# RMII_Ethernet.net
KiCad netlist of a schematic drawn in Altium Designer
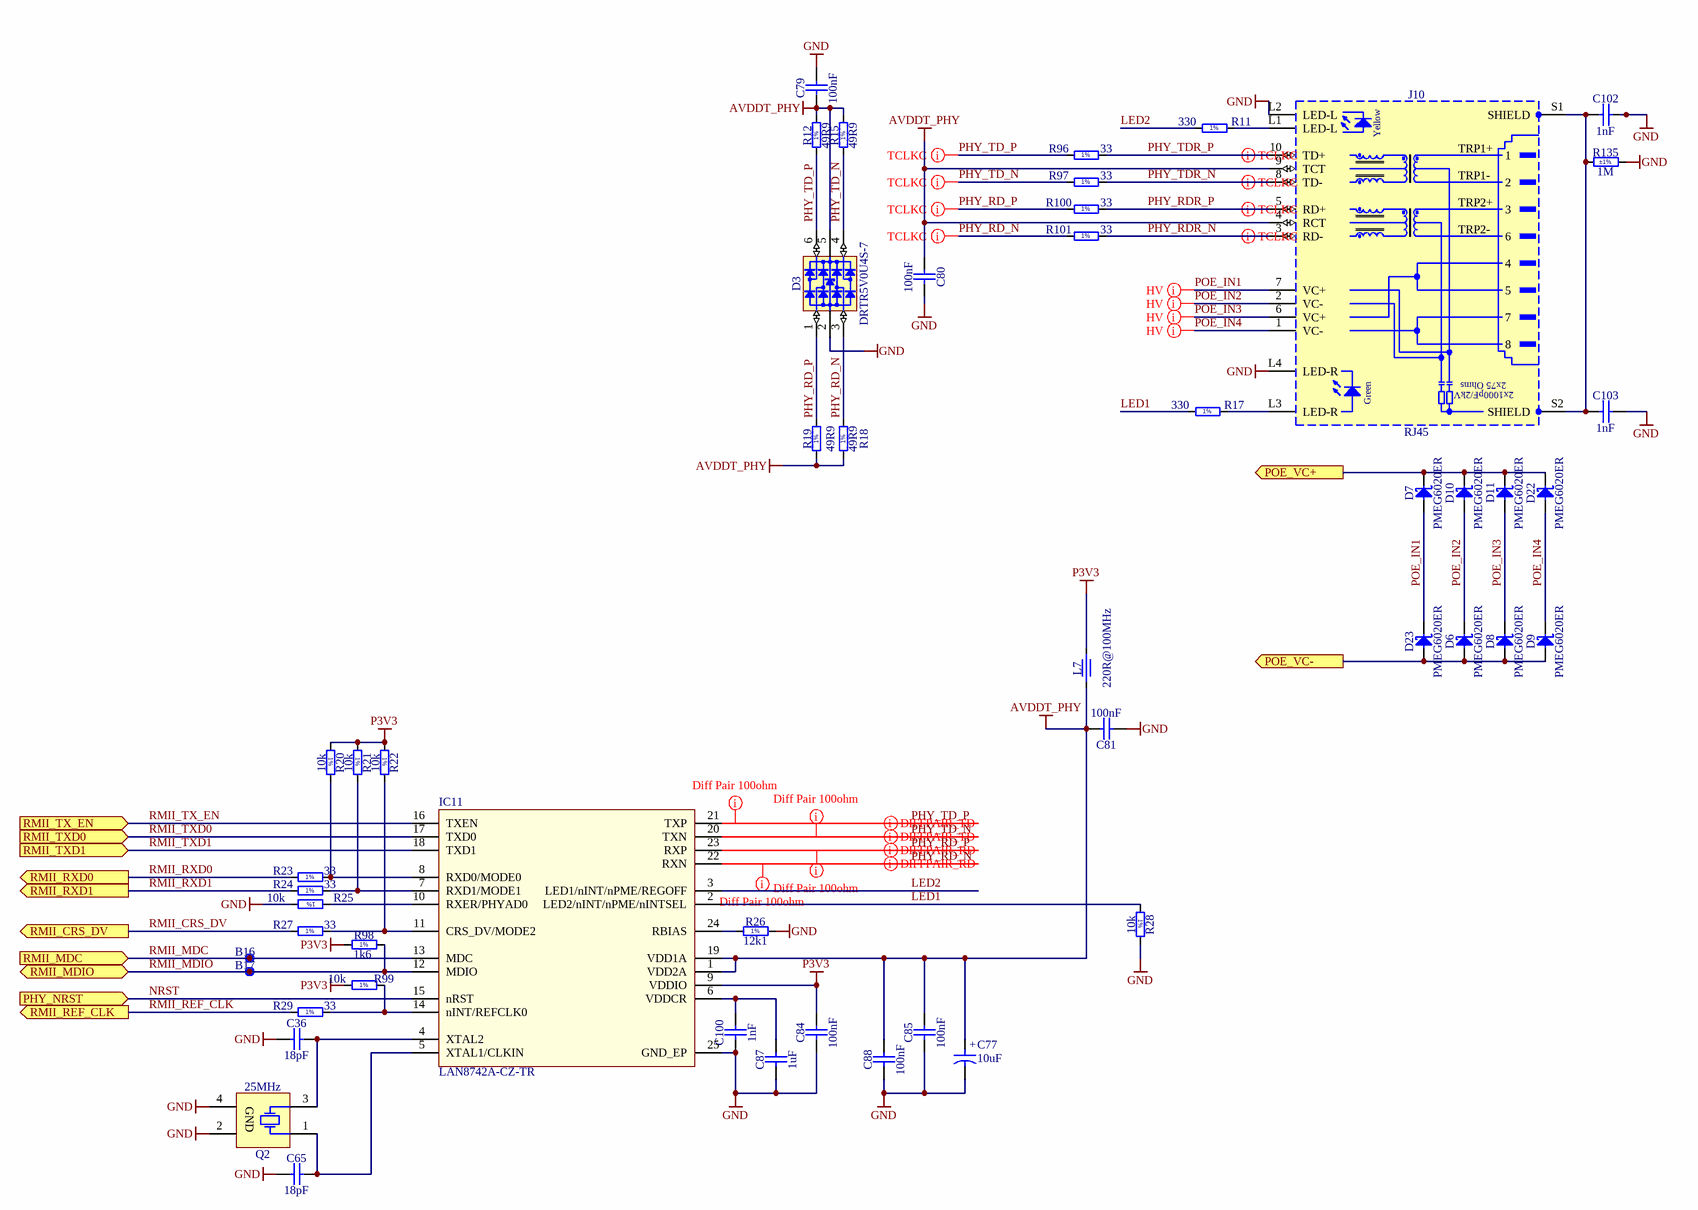
[diagram p0: RMII_Ethernet.SchDoc]

(export (version "E")
  (design (tool "Eeschema 10.0.6"))
  (components
    (comp (ref "B16")
      (value "SMD Pad")
      (footprint "C100")
      (description "Through Hole Pad")
      (fields (field (name "PART NUMBER") "SMD_PAD_D1MM") (field (name "AUTHOR") "CERN DEM JLC"))
      (libsource (lib "Eletro-mechanical") (part "Single SMD Pad (Round)"))
    )
    (comp (ref "B17")
      (value "SMD Pad")
      (footprint "C100")
      (description "Through Hole Pad")
      (fields (field (name "PART NUMBER") "SMD_PAD_D1MM") (field (name "AUTHOR") "CERN DEM JLC"))
      (libsource (lib "Eletro-mechanical") (part "Single SMD Pad (Round)"))
    )
    (comp (ref "C36")
      (value "18pF")
      (footprint "CAPC1005X55N")
      (description "Non-polarised capacitor")
      (fields
        (field (name "PART NUMBER") "CC0402_18PF_50V_5%_C0G")
        (field (name "VOLTAGE") "50V")
        (field (name "AUTHOR") "CERN DEM JLC")
      )
      (libsource (lib "Capacitors") (part "Capacitor - non polarized"))
    )
    (comp (ref "C65")
      (value "18pF")
      (footprint "CAPC1005X55N")
      (description "Non-polarised capacitor")
      (fields
        (field (name "PART NUMBER") "CC0402_18PF_50V_5%_C0G")
        (field (name "VOLTAGE") "50V")
        (field (name "AUTHOR") "CERN DEM JLC")
      )
      (libsource (lib "Capacitors") (part "Capacitor - non polarized"))
    )
    (comp (ref "C77")
      (value "10uF")
      (footprint "CAPMP3216X180N")
      (description "Polarised capacitor")
      (fields
        (field (name "PART NUMBER") "CTE3216-18_10UF_16V_20%_AVX_TCJ")
        (field (name "VOLTAGE") "16V")
        (field (name "AUTHOR") "CERN DEM JLC")
      )
      (libsource (lib "Capacitors") (part "Capacitor - polarized"))
    )
    (comp (ref "C79")
      (value "100nF")
      (footprint "CAPC1005X55N")
      (description "Non-polarised capacitor")
      (fields
        (field (name "PART NUMBER") "CC0402_100NF_16V_10%_X5R")
        (field (name "VOLTAGE") "16V")
        (field (name "AUTHOR") "CERN DEM JLC")
      )
      (libsource (lib "Capacitors") (part "Capacitor - non polarized"))
    )
    (comp (ref "C80")
      (value "100nF")
      (footprint "CAPC1005X55N")
      (description "Non-polarised capacitor")
      (fields
        (field (name "PART NUMBER") "CC0402_100NF_16V_10%_X5R")
        (field (name "VOLTAGE") "16V")
        (field (name "AUTHOR") "CERN DEM JLC")
      )
      (libsource (lib "Capacitors") (part "Capacitor - non polarized"))
    )
    (comp (ref "C81")
      (value "100nF")
      (footprint "CAPC1005X55N")
      (description "Non-polarised capacitor")
      (fields
        (field (name "PART NUMBER") "CC0402_100NF_16V_10%_X5R")
        (field (name "VOLTAGE") "16V")
        (field (name "AUTHOR") "CERN DEM JLC")
      )
      (libsource (lib "Capacitors") (part "Capacitor - non polarized"))
    )
    (comp (ref "C84")
      (value "100nF")
      (footprint "CAPC1005X55N")
      (description "Non-polarised capacitor")
      (fields
        (field (name "PART NUMBER") "CC0402_100NF_16V_10%_X5R")
        (field (name "VOLTAGE") "16V")
        (field (name "AUTHOR") "CERN DEM JLC")
      )
      (libsource (lib "Capacitors") (part "Capacitor - non polarized"))
    )
    (comp (ref "C85")
      (value "100nF")
      (footprint "CAPC1005X55N")
      (description "Non-polarised capacitor")
      (fields
        (field (name "PART NUMBER") "CC0402_100NF_16V_10%_X5R")
        (field (name "VOLTAGE") "16V")
        (field (name "AUTHOR") "CERN DEM JLC")
      )
      (libsource (lib "Capacitors") (part "Capacitor - non polarized"))
    )
    (comp (ref "C87")
      (value "1uF")
      (footprint "CAPC1608X87N")
      (description "Non-polarised capacitor")
      (fields
        (field (name "PART NUMBER") "CC0603_1UF_16V_10%_X7R")
        (field (name "VOLTAGE") "16V")
        (field (name "AUTHOR") "CERN DEM JLC")
      )
      (libsource (lib "Capacitors") (part "Capacitor - non polarized"))
    )
    (comp (ref "C88")
      (value "100nF")
      (footprint "CAPC1005X55N")
      (description "Non-polarised capacitor")
      (fields
        (field (name "PART NUMBER") "CC0402_100NF_16V_10%_X5R")
        (field (name "VOLTAGE") "16V")
        (field (name "AUTHOR") "CERN DEM JLC")
      )
      (libsource (lib "Capacitors") (part "Capacitor - non polarized"))
    )
    (comp (ref "C100")
      (value "1nF")
      (footprint "CAPC1005X55N")
      (description "Non-polarised capacitor")
      (fields
        (field (name "PART NUMBER") "CC0402_1NF_50V_10%_X7R")
        (field (name "VOLTAGE") "50V")
        (field (name "AUTHOR") "CERN DEM JLC")
      )
      (libsource (lib "Capacitors") (part "Capacitor - non polarized"))
    )
    (comp (ref "C102")
      (value "1nF")
      (footprint "CAPC2012X135N")
      (description "Non-polarised capacitor")
      (fields
        (field (name "PART NUMBER") "CC0805_1NF_50V_10%_X7R")
        (field (name "VOLTAGE") "50V")
        (field (name "AUTHOR") "CERN DEM JLC")
      )
      (libsource (lib "Capacitors") (part "Capacitor - non polarized"))
    )
    (comp (ref "C103")
      (value "1nF")
      (footprint "CAPC2012X135N")
      (description "Non-polarised capacitor")
      (fields
        (field (name "PART NUMBER") "CC0805_1NF_50V_10%_X7R")
        (field (name "VOLTAGE") "50V")
        (field (name "AUTHOR") "CERN DEM JLC")
      )
      (libsource (lib "Capacitors") (part "Capacitor - non polarized"))
    )
    (comp (ref "D3")
      (value "DRTR5V0U4S-7")
      (footprint "SOT65P210X110-6N")
      (description "Integrated Quad Ultra-Low Capacitance ESD Protection")
      (fields (field (name "MANUFACTURER") "DIODES") (field (name "AUTHOR") "GK"))
      (libsource (lib "Diodes") (part "D_TVS_DRTR5V0U4S-7"))
    )
    (comp (ref "D6")
      (value "PMEG6020ER")
      (footprint "SODFL3517X110N")
      (description "Schottky Diode")
      (fields
        (field (name "VOLTAGE") "60V")
        (field (name "POWER") "2A")
        (field (name "AUTHOR") "CERN DEM JMW")
      )
      (libsource (lib "ICs And Semiconductors") (part "Diode Schottky"))
    )
    (comp (ref "D7")
      (value "PMEG6020ER")
      (footprint "SODFL3517X110N")
      (description "Schottky Diode")
      (fields
        (field (name "VOLTAGE") "60V")
        (field (name "POWER") "2A")
        (field (name "AUTHOR") "CERN DEM JMW")
      )
      (libsource (lib "ICs And Semiconductors") (part "Diode Schottky"))
    )
    (comp (ref "D8")
      (value "PMEG6020ER")
      (footprint "SODFL3517X110N")
      (description "Schottky Diode")
      (fields
        (field (name "VOLTAGE") "60V")
        (field (name "POWER") "2A")
        (field (name "AUTHOR") "CERN DEM JMW")
      )
      (libsource (lib "ICs And Semiconductors") (part "Diode Schottky"))
    )
    (comp (ref "D9")
      (value "PMEG6020ER")
      (footprint "SODFL3517X110N")
      (description "Schottky Diode")
      (fields
        (field (name "VOLTAGE") "60V")
        (field (name "POWER") "2A")
        (field (name "AUTHOR") "CERN DEM JMW")
      )
      (libsource (lib "ICs And Semiconductors") (part "Diode Schottky"))
    )
    (comp (ref "D10")
      (value "PMEG6020ER")
      (footprint "SODFL3517X110N")
      (description "Schottky Diode")
      (fields
        (field (name "VOLTAGE") "60V")
        (field (name "POWER") "2A")
        (field (name "AUTHOR") "CERN DEM JMW")
      )
      (libsource (lib "ICs And Semiconductors") (part "Diode Schottky"))
    )
    (comp (ref "D11")
      (value "PMEG6020ER")
      (footprint "SODFL3517X110N")
      (description "Schottky Diode")
      (fields
        (field (name "VOLTAGE") "60V")
        (field (name "POWER") "2A")
        (field (name "AUTHOR") "CERN DEM JMW")
      )
      (libsource (lib "ICs And Semiconductors") (part "Diode Schottky"))
    )
    (comp (ref "D22")
      (value "PMEG6020ER")
      (footprint "SODFL3517X110N")
      (description "Schottky Diode")
      (fields
        (field (name "VOLTAGE") "60V")
        (field (name "POWER") "2A")
        (field (name "AUTHOR") "CERN DEM JMW")
      )
      (libsource (lib "ICs And Semiconductors") (part "Diode Schottky"))
    )
    (comp (ref "D23")
      (value "PMEG6020ER")
      (footprint "SODFL3517X110N")
      (description "Schottky Diode")
      (fields
        (field (name "VOLTAGE") "60V")
        (field (name "POWER") "2A")
        (field (name "AUTHOR") "CERN DEM JMW")
      )
      (libsource (lib "ICs And Semiconductors") (part "Diode Schottky"))
    )
    (comp (ref "IC11")
      (value "LAN8742A-CZ-TR")
      (footprint "QFN24_0R5_4X4")
      (libsource (lib "LIBRARY_SCH") (part "IFC_LAN8742A"))
    )
    (comp (ref "J10")
      (value "RJ45")
      (footprint "ABRACON_ARJM11C7-114-BA-EW2")
      (description "MagJack 10/100BaseT, PoE+, 1X1, OG/Y, -40 to 85*C, Tab Up, RoHS")
      (fields
        (field (name "PART NUMBER") "ARJM11C7-114-BA-EW2")
        (field (name "MANUFACTURER") "Abracon")
        (field (name "AUTHOR") "GK")
      )
      (libsource (lib "LIBRARY_SCH") (part "CON_ETH_POE_ARJM11C7"))
    )
    (comp (ref "L7")
      (value "220R@100MHz")
      (footprint "INDC1005X55N")
      (fields
        (field (name "PART NUMBER") "IND0402_MURATA_BLM15HB221SN1")
        (field (name "POWER") "250mA")
        (field (name "TOLERANCE") "±25%")
        (field (name "AUTHOR") "CERN DEM JLC")
      )
      (libsource (lib "Inductors & Transformers") (part "Ferrite Bead"))
    )
    (comp (ref "Q2")
      (value "25MHz")
      (footprint "XTAL_EPSON_TSX-3225")
      (description "Crystal 4 pins 1=XTAL Control 2=GND3=XTAL 4=GND")
      (fields
        (field (name "PART NUMBER") "XTAL_25MHZ_EPSON_TSX-3225 25.0000MF10Z-AC")
        (field (name "MANUFACTURER") "EPSON")
        (field (name "AUTHOR") "CERN DEM JLC")
      )
      (libsource (lib "ICs And Semiconductors") (part "Quartz Crystal 1X 2GND 3X 4GND"))
    )
    (comp (ref "R11")
      (value "330")
      (footprint "RESC1005X40N")
      (description "Resistor - 1%")
      (fields
        (field (name "PART NUMBER") "R0402_330R_1%_0.0625W_100PPM")
        (field (name "POWER") "0.0625W")
        (field (name "AUTHOR") "CERN DEM JLC")
      )
      (libsource (lib "Resistors") (part "Resistor - 1%"))
    )
    (comp (ref "R12")
      (value "49R9")
      (footprint "RESC1005X40N")
      (description "Resistor - 1%")
      (fields
        (field (name "PART NUMBER") "R0402_49R9_1%_0.0625W_100PPM")
        (field (name "POWER") "0.0625W")
        (field (name "AUTHOR") "CERN DEM JLC")
      )
      (libsource (lib "Resistors") (part "Resistor - 1%"))
    )
    (comp (ref "R15")
      (value "49R9")
      (footprint "RESC1005X40N")
      (description "Resistor - 1%")
      (fields
        (field (name "PART NUMBER") "R0402_49R9_1%_0.0625W_100PPM")
        (field (name "POWER") "0.0625W")
        (field (name "AUTHOR") "CERN DEM JLC")
      )
      (libsource (lib "Resistors") (part "Resistor - 1%"))
    )
    (comp (ref "R17")
      (value "330")
      (footprint "RESC1005X40N")
      (description "Resistor - 1%")
      (fields
        (field (name "PART NUMBER") "R0402_330R_1%_0.0625W_100PPM")
        (field (name "POWER") "0.0625W")
        (field (name "AUTHOR") "CERN DEM JLC")
      )
      (libsource (lib "Resistors") (part "Resistor - 1%"))
    )
    (comp (ref "R18")
      (value "49R9")
      (footprint "RESC1005X40N")
      (description "Resistor - 1%")
      (fields
        (field (name "PART NUMBER") "R0402_49R9_1%_0.0625W_100PPM")
        (field (name "POWER") "0.0625W")
        (field (name "AUTHOR") "CERN DEM JLC")
      )
      (libsource (lib "Resistors") (part "Resistor - 1%"))
    )
    (comp (ref "R19")
      (value "49R9")
      (footprint "RESC1005X40N")
      (description "Resistor - 1%")
      (fields
        (field (name "PART NUMBER") "R0402_49R9_1%_0.0625W_100PPM")
        (field (name "POWER") "0.0625W")
        (field (name "AUTHOR") "CERN DEM JLC")
      )
      (libsource (lib "Resistors") (part "Resistor - 1%"))
    )
    (comp (ref "R20")
      (value "10k")
      (footprint "RESC1005X40N")
      (description "Resistor - 1%")
      (fields
        (field (name "PART NUMBER") "R0402_10K_1%_0.0625W_100PPM")
        (field (name "POWER") "0.0625W")
        (field (name "AUTHOR") "CERN DEM JLC")
      )
      (libsource (lib "Resistors") (part "Resistor - 1%"))
    )
    (comp (ref "R21")
      (value "10k")
      (footprint "RESC1005X40N")
      (description "Resistor - 1%")
      (fields
        (field (name "PART NUMBER") "R0402_10K_1%_0.0625W_100PPM")
        (field (name "POWER") "0.0625W")
        (field (name "AUTHOR") "CERN DEM JLC")
      )
      (libsource (lib "Resistors") (part "Resistor - 1%"))
    )
    (comp (ref "R22")
      (value "10k")
      (footprint "RESC1005X40N")
      (description "Resistor - 1%")
      (fields
        (field (name "PART NUMBER") "R0402_10K_1%_0.0625W_100PPM")
        (field (name "POWER") "0.0625W")
        (field (name "AUTHOR") "CERN DEM JLC")
      )
      (libsource (lib "Resistors") (part "Resistor - 1%"))
    )
    (comp (ref "R23")
      (value "33")
      (footprint "RESC1005X40N")
      (description "Resistor - 1%")
      (fields
        (field (name "PART NUMBER") "R0402_33R_1%_0.0625W_100PPM")
        (field (name "POWER") "0.0625W")
        (field (name "AUTHOR") "CERN DEM JLC")
      )
      (libsource (lib "Resistors") (part "Resistor - 1%"))
    )
    (comp (ref "R24")
      (value "33")
      (footprint "RESC1005X40N")
      (description "Resistor - 1%")
      (fields
        (field (name "PART NUMBER") "R0402_33R_1%_0.0625W_100PPM")
        (field (name "POWER") "0.0625W")
        (field (name "AUTHOR") "CERN DEM JLC")
      )
      (libsource (lib "Resistors") (part "Resistor - 1%"))
    )
    (comp (ref "R25")
      (value "10k")
      (footprint "RESC1005X40N")
      (description "Resistor - 1%")
      (fields
        (field (name "PART NUMBER") "R0402_10K_1%_0.0625W_100PPM")
        (field (name "POWER") "0.0625W")
        (field (name "AUTHOR") "CERN DEM JLC")
      )
      (libsource (lib "Resistors") (part "Resistor - 1%"))
    )
    (comp (ref "R26")
      (value "12k1")
      (footprint "RESC1005X40N")
      (description "Resistor - 1%")
      (fields
        (field (name "PART NUMBER") "R0402_12K1_1%_0.0625W_100PPM")
        (field (name "POWER") "0.0625W")
        (field (name "AUTHOR") "CERN DEM JLC")
      )
      (libsource (lib "Resistors") (part "Resistor - 1%"))
    )
    (comp (ref "R27")
      (value "33")
      (footprint "RESC1005X40N")
      (description "Resistor - 1%")
      (fields
        (field (name "PART NUMBER") "R0402_33R_1%_0.0625W_100PPM")
        (field (name "POWER") "0.0625W")
        (field (name "AUTHOR") "CERN DEM JLC")
      )
      (libsource (lib "Resistors") (part "Resistor - 1%"))
    )
    (comp (ref "R28")
      (value "10k")
      (footprint "RESC1005X40N")
      (description "Resistor - 1%")
      (fields
        (field (name "PART NUMBER") "R0402_10K_1%_0.0625W_100PPM")
        (field (name "POWER") "0.0625W")
        (field (name "AUTHOR") "CERN DEM JLC")
      )
      (libsource (lib "Resistors") (part "Resistor - 1%"))
    )
    (comp (ref "R29")
      (value "33")
      (footprint "RESC1005X40N")
      (description "Resistor - 1%")
      (fields
        (field (name "PART NUMBER") "R0402_33R_1%_0.0625W_100PPM")
        (field (name "POWER") "0.0625W")
        (field (name "AUTHOR") "CERN DEM JLC")
      )
      (libsource (lib "Resistors") (part "Resistor - 1%"))
    )
    (comp (ref "R96")
      (value "33")
      (footprint "RESC1005X40N")
      (description "Resistor - 1%")
      (fields
        (field (name "PART NUMBER") "R0402_33R_1%_0.0625W_100PPM")
        (field (name "POWER") "0.0625W")
        (field (name "AUTHOR") "CERN DEM JLC")
      )
      (libsource (lib "Resistors") (part "Resistor - 1%"))
    )
    (comp (ref "R97")
      (value "33")
      (footprint "RESC1005X40N")
      (description "Resistor - 1%")
      (fields
        (field (name "PART NUMBER") "R0402_33R_1%_0.0625W_100PPM")
        (field (name "POWER") "0.0625W")
        (field (name "AUTHOR") "CERN DEM JLC")
      )
      (libsource (lib "Resistors") (part "Resistor - 1%"))
    )
    (comp (ref "R98")
      (value "1k6")
      (footprint "RESC1005X40N")
      (description "Resistor - 1%")
      (fields
        (field (name "PART NUMBER") "R0402_1K6_1%_0.0625W_100PPM")
        (field (name "POWER") "0.0625W")
        (field (name "AUTHOR") "CERN DEM JLC")
      )
      (libsource (lib "Resistors") (part "Resistor - 1%"))
    )
    (comp (ref "R99")
      (value "10k")
      (footprint "RESC1005X40N")
      (description "Resistor - 1%")
      (fields
        (field (name "PART NUMBER") "R0402_10K_1%_0.0625W_100PPM")
        (field (name "POWER") "0.0625W")
        (field (name "AUTHOR") "CERN DEM JLC")
      )
      (libsource (lib "Resistors") (part "Resistor - 1%"))
    )
    (comp (ref "R100")
      (value "33")
      (footprint "RESC1005X40N")
      (description "Resistor - 1%")
      (fields
        (field (name "PART NUMBER") "R0402_33R_1%_0.0625W_100PPM")
        (field (name "POWER") "0.0625W")
        (field (name "AUTHOR") "CERN DEM JLC")
      )
      (libsource (lib "Resistors") (part "Resistor - 1%"))
    )
    (comp (ref "R101")
      (value "33")
      (footprint "RESC1005X40N")
      (description "Resistor - 1%")
      (fields
        (field (name "PART NUMBER") "R0402_33R_1%_0.0625W_100PPM")
        (field (name "POWER") "0.0625W")
        (field (name "AUTHOR") "CERN DEM JLC")
      )
      (libsource (lib "Resistors") (part "Resistor - 1%"))
    )
    (comp (ref "R135")
      (value "1M")
      (footprint "RESC1608X55N")
      (description "Resistor - 1%")
      (fields
        (field (name "TOLERANCE") "±1%")
        (field (name "PART NUMBER") "R0603_1M_1%_0.1W_100PPM")
        (field (name "POWER") "0.1W")
        (field (name "AUTHOR") "CERN DEM JLC")
      )
      (libsource (lib "") (part "Resistor - 1%_1"))
    )
  )
  (nets
    (net (code "1") (name "/LED1") (class "Default")
      (node (ref "IC11") (pin "2") (pinfunction "LED2/nINT/nPME/nINTSEL_2") (pintype "passive"))
      (node (ref "R17") (pin "1") (pinfunction "1_1") (pintype "passive"))
      (node (ref "R28") (pin "1") (pinfunction "1_1") (pintype "passive"))
    )
    (net (code "2") (name "/LED2") (class "Default")
      (node (ref "IC11") (pin "3") (pinfunction "LED1/nINT/nPME/REGOFF_3") (pintype "passive"))
      (node (ref "R11") (pin "1") (pinfunction "1_1") (pintype "passive"))
    )
    (net (code "3") (name "/NRST") (class "Default")
      (node (ref "IC11") (pin "15") (pinfunction "nRST_15") (pintype "passive"))
    )
    (net (code "4") (name "/PHY_RDR_N") (class "Default")
      (node (ref "J10") (pin "3") (pinfunction "RD-_3") (pintype "bidirectional"))
      (node (ref "R101") (pin "2") (pinfunction "2_2") (pintype "passive"))
    )
    (net (code "5") (name "/PHY_RDR_P") (class "Default")
      (node (ref "J10") (pin "5") (pinfunction "RD+_5") (pintype "bidirectional"))
      (node (ref "R100") (pin "2") (pinfunction "2_2") (pintype "passive"))
    )
    (net (code "6") (name "/PHY_RD_N") (class "Default")
      (node (ref "D3") (pin "3") (pinfunction "I/O2_3") (pintype "bidirectional"))
      (node (ref "IC11") (pin "22") (pinfunction "RXN_22") (pintype "passive"))
      (node (ref "R101") (pin "1") (pinfunction "1_1") (pintype "passive"))
      (node (ref "R18") (pin "2") (pinfunction "2_2") (pintype "passive"))
    )
    (net (code "7") (name "/PHY_RD_P") (class "Default")
      (node (ref "D3") (pin "1") (pinfunction "I/O1_1") (pintype "bidirectional"))
      (node (ref "IC11") (pin "23") (pinfunction "RXP_23") (pintype "passive"))
      (node (ref "R100") (pin "1") (pinfunction "1_1") (pintype "passive"))
      (node (ref "R19") (pin "2") (pinfunction "2_2") (pintype "passive"))
    )
    (net (code "8") (name "/PHY_TDR_N") (class "Default")
      (node (ref "J10") (pin "8") (pinfunction "TD-_8") (pintype "bidirectional"))
      (node (ref "R97") (pin "2") (pinfunction "2_2") (pintype "passive"))
    )
    (net (code "9") (name "/PHY_TDR_P") (class "Default")
      (node (ref "J10") (pin "10") (pinfunction "TD+_10") (pintype "bidirectional"))
      (node (ref "R96") (pin "2") (pinfunction "2_2") (pintype "passive"))
    )
    (net (code "10") (name "/PHY_TD_N") (class "Default")
      (node (ref "D3") (pin "4") (pinfunction "I/O3_4") (pintype "bidirectional"))
      (node (ref "IC11") (pin "20") (pinfunction "TXN_20") (pintype "passive"))
      (node (ref "R15") (pin "1") (pinfunction "1_1") (pintype "passive"))
      (node (ref "R97") (pin "1") (pinfunction "1_1") (pintype "passive"))
    )
    (net (code "11") (name "/PHY_TD_P") (class "Default")
      (node (ref "D3") (pin "6") (pinfunction "I/O4_6") (pintype "bidirectional"))
      (node (ref "IC11") (pin "21") (pinfunction "TXP_21") (pintype "passive"))
      (node (ref "R12") (pin "1") (pinfunction "1_1") (pintype "passive"))
      (node (ref "R96") (pin "1") (pinfunction "1_1") (pintype "passive"))
    )
    (net (code "12") (name "/POE_IN1") (class "Default")
      (node (ref "D23") (pin "1") (pinfunction "C_1") (pintype "passive"))
      (node (ref "D7") (pin "2") (pinfunction "A_2") (pintype "passive"))
      (node (ref "J10") (pin "7") (pinfunction "VC+_7") (pintype "passive"))
    )
    (net (code "13") (name "/POE_IN2") (class "Default")
      (node (ref "D10") (pin "2") (pinfunction "A_2") (pintype "passive"))
      (node (ref "D6") (pin "1") (pinfunction "C_1") (pintype "passive"))
      (node (ref "J10") (pin "2") (pinfunction "VC-_2") (pintype "passive"))
    )
    (net (code "14") (name "/POE_IN3") (class "Default")
      (node (ref "D11") (pin "2") (pinfunction "A_2") (pintype "passive"))
      (node (ref "D8") (pin "1") (pinfunction "C_1") (pintype "passive"))
      (node (ref "J10") (pin "6") (pinfunction "VC+_6") (pintype "passive"))
    )
    (net (code "15") (name "/POE_IN4") (class "Default")
      (node (ref "D22") (pin "2") (pinfunction "A_2") (pintype "passive"))
      (node (ref "D9") (pin "1") (pinfunction "C_1") (pintype "passive"))
      (node (ref "J10") (pin "1") (pinfunction "VC-_1") (pintype "passive"))
    )
    (net (code "16") (name "/POE_VC+") (class "Default")
      (node (ref "D10") (pin "1") (pinfunction "C_1") (pintype "passive"))
      (node (ref "D11") (pin "1") (pinfunction "C_1") (pintype "passive"))
      (node (ref "D22") (pin "1") (pinfunction "C_1") (pintype "passive"))
      (node (ref "D7") (pin "1") (pinfunction "C_1") (pintype "passive"))
    )
    (net (code "17") (name "/POE_VC-") (class "Default")
      (node (ref "D23") (pin "2") (pinfunction "A_2") (pintype "passive"))
      (node (ref "D6") (pin "2") (pinfunction "A_2") (pintype "passive"))
      (node (ref "D8") (pin "2") (pinfunction "A_2") (pintype "passive"))
      (node (ref "D9") (pin "2") (pinfunction "A_2") (pintype "passive"))
    )
    (net (code "18") (name "/RMII_CRS_DV") (class "Default")
      (node (ref "R27") (pin "1") (pinfunction "1_1") (pintype "passive"))
    )
    (net (code "19") (name "/RMII_MDC") (class "Default")
      (node (ref "B16") (pin "1") (pinfunction "1_1") (pintype "bidirectional"))
      (node (ref "IC11") (pin "13") (pinfunction "MDC_13") (pintype "passive"))
    )
    (net (code "20") (name "/RMII_MDIO") (class "Default")
      (node (ref "B17") (pin "1") (pinfunction "1_1") (pintype "bidirectional"))
      (node (ref "IC11") (pin "12") (pinfunction "MDIO_12") (pintype "passive"))
      (node (ref "R98") (pin "2") (pinfunction "2_2") (pintype "passive"))
    )
    (net (code "21") (name "/RMII_REF_CLK") (class "Default")
      (node (ref "R29") (pin "1") (pinfunction "1_1") (pintype "passive"))
    )
    (net (code "22") (name "/RMII_RXD0") (class "Default")
      (node (ref "R23") (pin "1") (pinfunction "1_1") (pintype "passive"))
    )
    (net (code "23") (name "/RMII_RXD1") (class "Default")
      (node (ref "R24") (pin "1") (pinfunction "1_1") (pintype "passive"))
    )
    (net (code "24") (name "/RMII_TXD0") (class "Default")
      (node (ref "IC11") (pin "17") (pinfunction "TXD0_17") (pintype "passive"))
    )
    (net (code "25") (name "/RMII_TXD1") (class "Default")
      (node (ref "IC11") (pin "18") (pinfunction "TXD1_18") (pintype "passive"))
    )
    (net (code "26") (name "/RMII_TX_EN") (class "Default")
      (node (ref "IC11") (pin "16") (pinfunction "TXEN_16") (pintype "passive"))
    )
    (net (code "27") (name "AVDDT_PHY") (class "Default")
      (node (ref "C77") (pin "1") (pinfunction "1_1") (pintype "passive"))
      (node (ref "C79") (pin "1") (pinfunction "1_1") (pintype "passive"))
      (node (ref "C80") (pin "2") (pinfunction "2_2") (pintype "passive"))
      (node (ref "C81") (pin "2") (pinfunction "2_2") (pintype "passive"))
      (node (ref "C85") (pin "2") (pinfunction "2_2") (pintype "passive"))
      (node (ref "C88") (pin "2") (pinfunction "2_2") (pintype "passive"))
      (node (ref "D3") (pin "5") (pinfunction "VBUS_5") (pintype "power_in"))
      (node (ref "IC11") (pin "1") (pinfunction "VDD2A_1") (pintype "passive"))
      (node (ref "IC11") (pin "19") (pinfunction "VDD1A_19") (pintype "passive"))
      (node (ref "J10") (pin "4") (pinfunction "RCT_4") (pintype "bidirectional"))
      (node (ref "J10") (pin "9") (pinfunction "TCT_9") (pintype "bidirectional"))
      (node (ref "L7") (pin "1") (pinfunction "1_1") (pintype "passive"))
      (node (ref "R12") (pin "2") (pinfunction "2_2") (pintype "passive"))
      (node (ref "R15") (pin "2") (pinfunction "2_2") (pintype "passive"))
      (node (ref "R18") (pin "1") (pinfunction "1_1") (pintype "passive"))
      (node (ref "R19") (pin "1") (pinfunction "1_1") (pintype "passive"))
    )
    (net (code "28") (name "GND") (class "Default")
      (node (ref "C100") (pin "1") (pinfunction "1_1") (pintype "passive"))
      (node (ref "C102") (pin "2") (pinfunction "2_2") (pintype "passive"))
      (node (ref "C103") (pin "2") (pinfunction "2_2") (pintype "passive"))
      (node (ref "C36") (pin "1") (pinfunction "1_1") (pintype "passive"))
      (node (ref "C65") (pin "1") (pinfunction "1_1") (pintype "passive"))
      (node (ref "C77") (pin "2") (pinfunction "2_2") (pintype "passive"))
      (node (ref "C79") (pin "2") (pinfunction "2_2") (pintype "passive"))
      (node (ref "C80") (pin "1") (pinfunction "1_1") (pintype "passive"))
      (node (ref "C81") (pin "1") (pinfunction "1_1") (pintype "passive"))
      (node (ref "C84") (pin "1") (pinfunction "1_1") (pintype "passive"))
      (node (ref "C85") (pin "1") (pinfunction "1_1") (pintype "passive"))
      (node (ref "C87") (pin "1") (pinfunction "1_1") (pintype "passive"))
      (node (ref "C88") (pin "1") (pinfunction "1_1") (pintype "passive"))
      (node (ref "D3") (pin "2") (pinfunction "GND_2") (pintype "power_in"))
      (node (ref "IC11") (pin "25") (pinfunction "GND_EP_25") (pintype "passive"))
      (node (ref "J10") (pin "L2") (pinfunction "LED-L_L2") (pintype "passive"))
      (node (ref "J10") (pin "L4") (pinfunction "LED-R_L4") (pintype "passive"))
      (node (ref "Q2") (pin "2") (pinfunction "GND_2") (pintype "power_in"))
      (node (ref "Q2") (pin "4") (pinfunction "GND_4") (pintype "power_in"))
      (node (ref "R135") (pin "2") (pinfunction "2_2") (pintype "passive"))
      (node (ref "R25") (pin "2") (pinfunction "2_2") (pintype "passive"))
      (node (ref "R26") (pin "2") (pinfunction "2_2") (pintype "passive"))
      (node (ref "R28") (pin "2") (pinfunction "2_2") (pintype "passive"))
    )
    (net (code "29") (name "Net-(C102-Pad1)") (class "Default")
      (node (ref "C102") (pin "1") (pinfunction "1_1") (pintype "passive"))
      (node (ref "C103") (pin "1") (pinfunction "1_1") (pintype "passive"))
      (node (ref "J10") (pin "S1") (pinfunction "SHIELD_S1") (pintype "power_in"))
      (node (ref "J10") (pin "S2") (pinfunction "SHIELD_S2") (pintype "power_in"))
      (node (ref "R135") (pin "1") (pinfunction "1_1") (pintype "passive"))
    )
    (net (code "30") (name "Net-(IC11-CRS_DV{slash}MODE2)") (class "Default")
      (node (ref "IC11") (pin "11") (pinfunction "CRS_DV/MODE2_11") (pintype "passive"))
      (node (ref "R22") (pin "2") (pinfunction "2_2") (pintype "passive"))
      (node (ref "R27") (pin "2") (pinfunction "2_2") (pintype "passive"))
    )
    (net (code "31") (name "Net-(IC11-RBIAS)") (class "Default")
      (node (ref "IC11") (pin "24") (pinfunction "RBIAS_24") (pintype "passive"))
      (node (ref "R26") (pin "1") (pinfunction "1_1") (pintype "passive"))
    )
    (net (code "32") (name "Net-(IC11-RXD0{slash}MODE0)") (class "Default")
      (node (ref "IC11") (pin "8") (pinfunction "RXD0/MODE0_8") (pintype "passive"))
      (node (ref "R20") (pin "2") (pinfunction "2_2") (pintype "passive"))
      (node (ref "R23") (pin "2") (pinfunction "2_2") (pintype "passive"))
    )
    (net (code "33") (name "Net-(IC11-RXD1{slash}MODE1)") (class "Default")
      (node (ref "IC11") (pin "7") (pinfunction "RXD1/MODE1_7") (pintype "passive"))
      (node (ref "R21") (pin "2") (pinfunction "2_2") (pintype "passive"))
      (node (ref "R24") (pin "2") (pinfunction "2_2") (pintype "passive"))
    )
    (net (code "34") (name "Net-(IC11-RXER{slash}PHYAD0)") (class "Default")
      (node (ref "IC11") (pin "10") (pinfunction "RXER/PHYAD0_10") (pintype "passive"))
      (node (ref "R25") (pin "1") (pinfunction "1_1") (pintype "passive"))
    )
    (net (code "35") (name "Net-(IC11-VDDCR)") (class "Default")
      (node (ref "C100") (pin "2") (pinfunction "2_2") (pintype "passive"))
      (node (ref "C87") (pin "2") (pinfunction "2_2") (pintype "passive"))
      (node (ref "IC11") (pin "6") (pinfunction "VDDCR_6") (pintype "passive"))
    )
    (net (code "36") (name "Net-(IC11-XTAL1{slash}CLKIN)") (class "Default")
      (node (ref "C65") (pin "2") (pinfunction "2_2") (pintype "passive"))
      (node (ref "IC11") (pin "5") (pinfunction "XTAL1/CLKIN_5") (pintype "passive"))
      (node (ref "Q2") (pin "1") (pinfunction "X_1") (pintype "passive"))
    )
    (net (code "37") (name "Net-(IC11-XTAL2)") (class "Default")
      (node (ref "C36") (pin "2") (pinfunction "2_2") (pintype "passive"))
      (node (ref "IC11") (pin "4") (pinfunction "XTAL2_4") (pintype "passive"))
      (node (ref "Q2") (pin "3") (pinfunction "X_3") (pintype "passive"))
    )
    (net (code "38") (name "Net-(IC11-nINT{slash}REFCLK0)") (class "Default")
      (node (ref "IC11") (pin "14") (pinfunction "nINT/REFCLK0_14") (pintype "passive"))
      (node (ref "R29") (pin "2") (pinfunction "2_2") (pintype "passive"))
      (node (ref "R99") (pin "2") (pinfunction "2_2") (pintype "passive"))
    )
    (net (code "39") (name "Net-(J10-LED-L-PadL1)") (class "Default")
      (node (ref "J10") (pin "L1") (pinfunction "LED-L_L1") (pintype "passive"))
      (node (ref "R11") (pin "2") (pinfunction "2_2") (pintype "passive"))
    )
    (net (code "40") (name "Net-(J10-LED-R-PadL3)") (class "Default")
      (node (ref "J10") (pin "L3") (pinfunction "LED-R_L3") (pintype "passive"))
      (node (ref "R17") (pin "2") (pinfunction "2_2") (pintype "passive"))
    )
    (net (code "41") (name "P3V3") (class "Default")
      (node (ref "C84") (pin "2") (pinfunction "2_2") (pintype "passive"))
      (node (ref "IC11") (pin "9") (pinfunction "VDDIO_9") (pintype "passive"))
      (node (ref "L7") (pin "2") (pinfunction "2_2") (pintype "passive"))
      (node (ref "R20") (pin "1") (pinfunction "1_1") (pintype "passive"))
      (node (ref "R21") (pin "1") (pinfunction "1_1") (pintype "passive"))
      (node (ref "R22") (pin "1") (pinfunction "1_1") (pintype "passive"))
      (node (ref "R98") (pin "1") (pinfunction "1_1") (pintype "passive"))
      (node (ref "R99") (pin "1") (pinfunction "1_1") (pintype "passive"))
    )
  )
)
